# SoC_PS_504_DDR4.net
KiCad netlist of a schematic drawn in Altium Designer
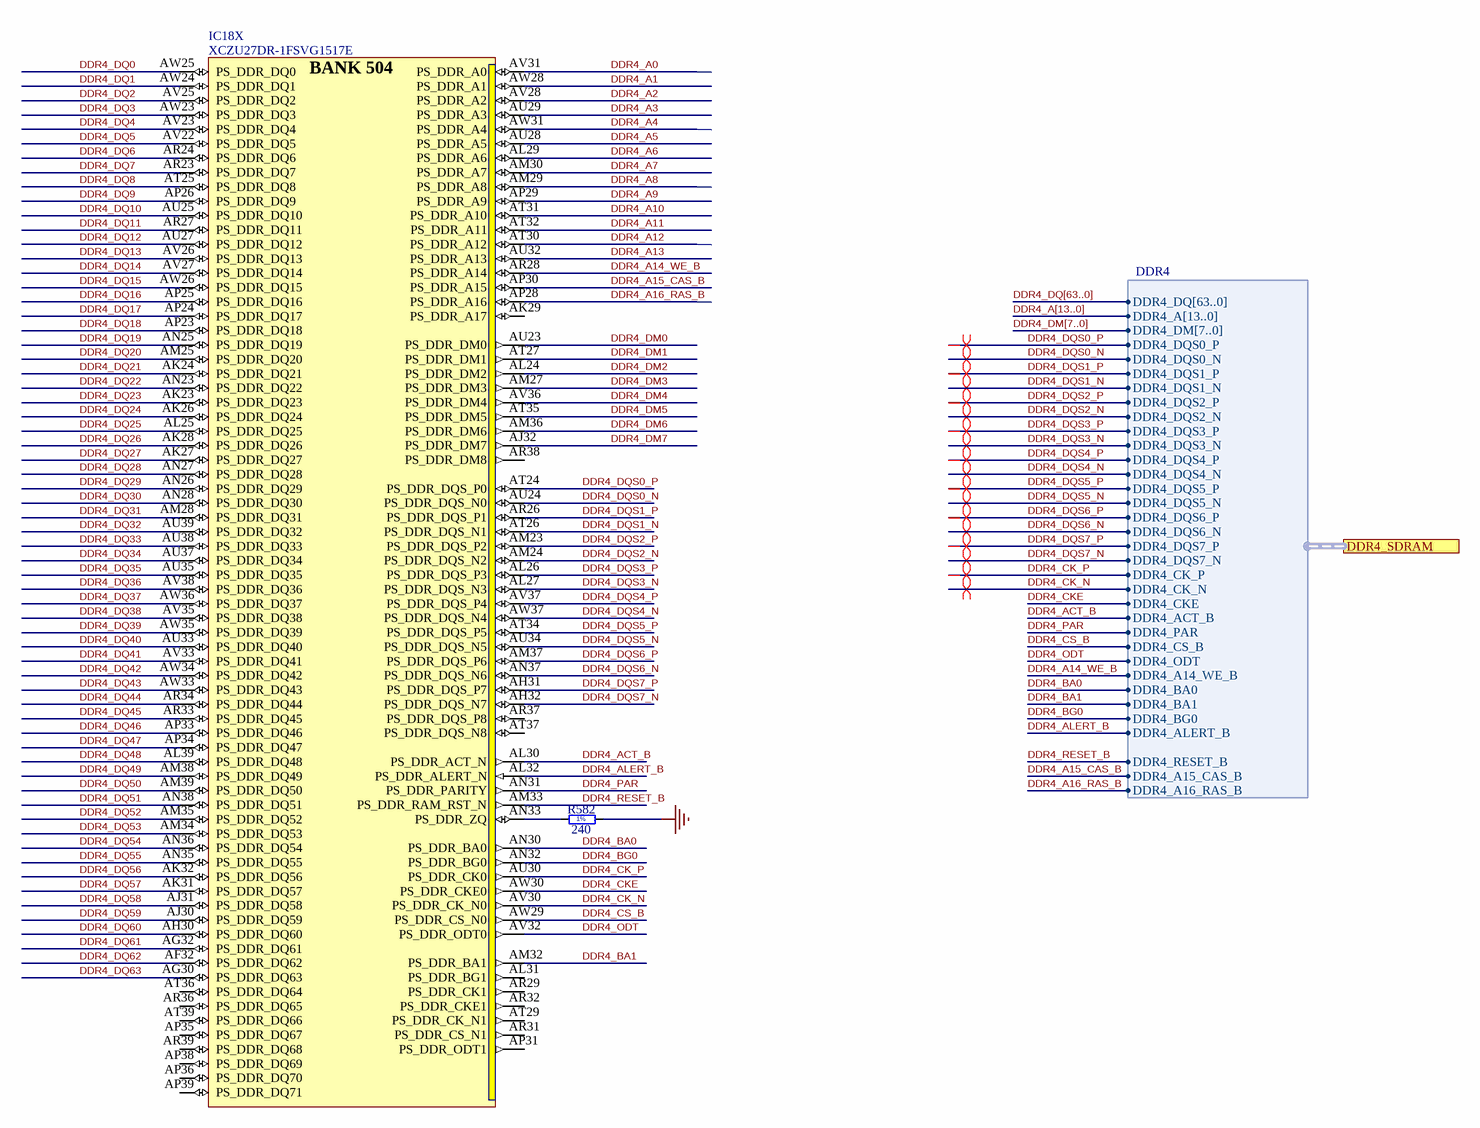
[diagram p0: SoC_PS_504_DDR4.SchDoc]

(export (version "E")
  (design (tool "Eeschema 10.0.6"))
  (components
    (comp (ref "IC18")
      (value "XCZU27DR-1FSVG1517E")
      (footprint "XILINX_FSVG1517 (XCZU27DR)")
      (fields (field (name "MANUFACTURER") "XILINX") (field (name "AUTHOR") "CERN DEM MR"))
      (libsource (lib "ICs And Semiconductors") (part "XCZU27DR-1FSVG1517E"))
    )
    (comp (ref "R582")
      (value "240")
      (footprint "RESC1005X40N")
      (description "Resistor - 1%")
      (fields
        (field (name "MANUFACTURER PART NUMBER") "R0402_240R_1%_0.0625W_100PPM")
        (field (name "MANUFACTURER") "GENERIC")
        (field (name "AUTHOR") "CERN DEM JLC")
      )
      (libsource (lib "Resistors") (part "Resistor - 1%"))
    )
  )
  (nets
    (net (code "2") (name "/DDR4_A0") (class "Default")
      (node (ref "IC18") (pin "AV31") (pinfunction "PS_DDR_A0_AV31") (pintype "bidirectional"))
    )
    (net (code "3") (name "/DDR4_A1") (class "Default")
      (node (ref "IC18") (pin "AW28") (pinfunction "PS_DDR_A1_AW28") (pintype "bidirectional"))
    )
    (net (code "4") (name "/DDR4_A2") (class "Default")
      (node (ref "IC18") (pin "AV28") (pinfunction "PS_DDR_A2_AV28") (pintype "bidirectional"))
    )
    (net (code "5") (name "/DDR4_A3") (class "Default")
      (node (ref "IC18") (pin "AU29") (pinfunction "PS_DDR_A3_AU29") (pintype "bidirectional"))
    )
    (net (code "6") (name "/DDR4_A4") (class "Default")
      (node (ref "IC18") (pin "AW31") (pinfunction "PS_DDR_A4_AW31") (pintype "bidirectional"))
    )
    (net (code "7") (name "/DDR4_A5") (class "Default")
      (node (ref "IC18") (pin "AU28") (pinfunction "PS_DDR_A5_AU28") (pintype "bidirectional"))
    )
    (net (code "8") (name "/DDR4_A6") (class "Default")
      (node (ref "IC18") (pin "AL29") (pinfunction "PS_DDR_A6_AL29") (pintype "bidirectional"))
    )
    (net (code "9") (name "/DDR4_A7") (class "Default")
      (node (ref "IC18") (pin "AM30") (pinfunction "PS_DDR_A7_AM30") (pintype "bidirectional"))
    )
    (net (code "10") (name "/DDR4_A8") (class "Default")
      (node (ref "IC18") (pin "AM29") (pinfunction "PS_DDR_A8_AM29") (pintype "bidirectional"))
    )
    (net (code "11") (name "/DDR4_A9") (class "Default")
      (node (ref "IC18") (pin "AP29") (pinfunction "PS_DDR_A9_AP29") (pintype "bidirectional"))
    )
    (net (code "12") (name "/DDR4_A10") (class "Default")
      (node (ref "IC18") (pin "AT31") (pinfunction "PS_DDR_A10_AT31") (pintype "bidirectional"))
    )
    (net (code "13") (name "/DDR4_A11") (class "Default")
      (node (ref "IC18") (pin "AT32") (pinfunction "PS_DDR_A11_AT32") (pintype "bidirectional"))
    )
    (net (code "14") (name "/DDR4_A12") (class "Default")
      (node (ref "IC18") (pin "AT30") (pinfunction "PS_DDR_A12_AT30") (pintype "bidirectional"))
    )
    (net (code "15") (name "/DDR4_A13") (class "Default")
      (node (ref "IC18") (pin "AU32") (pinfunction "PS_DDR_A13_AU32") (pintype "bidirectional"))
    )
    (net (code "16") (name "/DDR4_A14_WE_B") (class "Default")
      (node (ref "IC18") (pin "AR28") (pinfunction "PS_DDR_A14_AR28") (pintype "bidirectional"))
    )
    (net (code "17") (name "/DDR4_A15_CAS_B") (class "Default")
      (node (ref "IC18") (pin "AP30") (pinfunction "PS_DDR_A15_AP30") (pintype "bidirectional"))
    )
    (net (code "18") (name "/DDR4_A16_RAS_B") (class "Default")
      (node (ref "IC18") (pin "AP28") (pinfunction "PS_DDR_A16_AP28") (pintype "bidirectional"))
    )
    (net (code "19") (name "/DDR4_ACT_B") (class "Default")
      (node (ref "IC18") (pin "AL30") (pinfunction "PS_DDR_ACT_N_AL30") (pintype "output"))
    )
    (net (code "20") (name "/DDR4_ALERT_B") (class "Default")
      (node (ref "IC18") (pin "AL32") (pinfunction "PS_DDR_ALERT_N_AL32") (pintype "input"))
    )
    (net (code "22") (name "/DDR4_BA0") (class "Default")
      (node (ref "IC18") (pin "AN30") (pinfunction "PS_DDR_BA0_AN30") (pintype "output"))
    )
    (net (code "23") (name "/DDR4_BA1") (class "Default")
      (node (ref "IC18") (pin "AM32") (pinfunction "PS_DDR_BA1_AM32") (pintype "output"))
    )
    (net (code "24") (name "/DDR4_BG0") (class "Default")
      (node (ref "IC18") (pin "AN32") (pinfunction "PS_DDR_BG0_AN32") (pintype "output"))
    )
    (net (code "25") (name "/DDR4_CKE") (class "Default")
      (node (ref "IC18") (pin "AW30") (pinfunction "PS_DDR_CKE0_AW30") (pintype "output"))
    )
    (net (code "26") (name "/DDR4_CK_N") (class "Default")
      (node (ref "IC18") (pin "AV30") (pinfunction "PS_DDR_CK_N0_AV30") (pintype "output"))
    )
    (net (code "27") (name "/DDR4_CK_P") (class "Default")
      (node (ref "IC18") (pin "AU30") (pinfunction "PS_DDR_CK0_AU30") (pintype "output"))
    )
    (net (code "28") (name "/DDR4_CS_B") (class "Default")
      (node (ref "IC18") (pin "AW29") (pinfunction "PS_DDR_CS_N0_AW29") (pintype "output"))
    )
    (net (code "29") (name "/DDR4_DM0") (class "Default")
      (node (ref "IC18") (pin "AU23") (pinfunction "PS_DDR_DM0_AU23") (pintype "output"))
    )
    (net (code "30") (name "/DDR4_DM1") (class "Default")
      (node (ref "IC18") (pin "AT27") (pinfunction "PS_DDR_DM1_AT27") (pintype "output"))
    )
    (net (code "31") (name "/DDR4_DM2") (class "Default")
      (node (ref "IC18") (pin "AL24") (pinfunction "PS_DDR_DM2_AL24") (pintype "output"))
    )
    (net (code "32") (name "/DDR4_DM3") (class "Default")
      (node (ref "IC18") (pin "AM27") (pinfunction "PS_DDR_DM3_AM27") (pintype "output"))
    )
    (net (code "33") (name "/DDR4_DM4") (class "Default")
      (node (ref "IC18") (pin "AV36") (pinfunction "PS_DDR_DM4_AV36") (pintype "output"))
    )
    (net (code "34") (name "/DDR4_DM5") (class "Default")
      (node (ref "IC18") (pin "AT35") (pinfunction "PS_DDR_DM5_AT35") (pintype "output"))
    )
    (net (code "35") (name "/DDR4_DM6") (class "Default")
      (node (ref "IC18") (pin "AM36") (pinfunction "PS_DDR_DM6_AM36") (pintype "output"))
    )
    (net (code "36") (name "/DDR4_DM7") (class "Default")
      (node (ref "IC18") (pin "AJ32") (pinfunction "PS_DDR_DM7_AJ32") (pintype "output"))
    )
    (net (code "38") (name "/DDR4_DQ0") (class "Default")
      (node (ref "IC18") (pin "AW25") (pinfunction "PS_DDR_DQ0_AW25") (pintype "bidirectional"))
    )
    (net (code "39") (name "/DDR4_DQ1") (class "Default")
      (node (ref "IC18") (pin "AW24") (pinfunction "PS_DDR_DQ1_AW24") (pintype "bidirectional"))
    )
    (net (code "40") (name "/DDR4_DQ2") (class "Default")
      (node (ref "IC18") (pin "AV25") (pinfunction "PS_DDR_DQ2_AV25") (pintype "bidirectional"))
    )
    (net (code "41") (name "/DDR4_DQ3") (class "Default")
      (node (ref "IC18") (pin "AW23") (pinfunction "PS_DDR_DQ3_AW23") (pintype "bidirectional"))
    )
    (net (code "42") (name "/DDR4_DQ4") (class "Default")
      (node (ref "IC18") (pin "AV23") (pinfunction "PS_DDR_DQ4_AV23") (pintype "bidirectional"))
    )
    (net (code "43") (name "/DDR4_DQ5") (class "Default")
      (node (ref "IC18") (pin "AV22") (pinfunction "PS_DDR_DQ5_AV22") (pintype "bidirectional"))
    )
    (net (code "44") (name "/DDR4_DQ6") (class "Default")
      (node (ref "IC18") (pin "AR24") (pinfunction "PS_DDR_DQ6_AR24") (pintype "bidirectional"))
    )
    (net (code "45") (name "/DDR4_DQ7") (class "Default")
      (node (ref "IC18") (pin "AR23") (pinfunction "PS_DDR_DQ7_AR23") (pintype "bidirectional"))
    )
    (net (code "46") (name "/DDR4_DQ8") (class "Default")
      (node (ref "IC18") (pin "AT25") (pinfunction "PS_DDR_DQ8_AT25") (pintype "bidirectional"))
    )
    (net (code "47") (name "/DDR4_DQ9") (class "Default")
      (node (ref "IC18") (pin "AP26") (pinfunction "PS_DDR_DQ9_AP26") (pintype "bidirectional"))
    )
    (net (code "48") (name "/DDR4_DQ10") (class "Default")
      (node (ref "IC18") (pin "AU25") (pinfunction "PS_DDR_DQ10_AU25") (pintype "bidirectional"))
    )
    (net (code "49") (name "/DDR4_DQ11") (class "Default")
      (node (ref "IC18") (pin "AR27") (pinfunction "PS_DDR_DQ11_AR27") (pintype "bidirectional"))
    )
    (net (code "50") (name "/DDR4_DQ12") (class "Default")
      (node (ref "IC18") (pin "AU27") (pinfunction "PS_DDR_DQ12_AU27") (pintype "bidirectional"))
    )
    (net (code "51") (name "/DDR4_DQ13") (class "Default")
      (node (ref "IC18") (pin "AV26") (pinfunction "PS_DDR_DQ13_AV26") (pintype "bidirectional"))
    )
    (net (code "52") (name "/DDR4_DQ14") (class "Default")
      (node (ref "IC18") (pin "AV27") (pinfunction "PS_DDR_DQ14_AV27") (pintype "bidirectional"))
    )
    (net (code "53") (name "/DDR4_DQ15") (class "Default")
      (node (ref "IC18") (pin "AW26") (pinfunction "PS_DDR_DQ15_AW26") (pintype "bidirectional"))
    )
    (net (code "54") (name "/DDR4_DQ16") (class "Default")
      (node (ref "IC18") (pin "AP25") (pinfunction "PS_DDR_DQ16_AP25") (pintype "bidirectional"))
    )
    (net (code "55") (name "/DDR4_DQ17") (class "Default")
      (node (ref "IC18") (pin "AP24") (pinfunction "PS_DDR_DQ17_AP24") (pintype "bidirectional"))
    )
    (net (code "56") (name "/DDR4_DQ18") (class "Default")
      (node (ref "IC18") (pin "AP23") (pinfunction "PS_DDR_DQ18_AP23") (pintype "bidirectional"))
    )
    (net (code "57") (name "/DDR4_DQ19") (class "Default")
      (node (ref "IC18") (pin "AN25") (pinfunction "PS_DDR_DQ19_AN25") (pintype "bidirectional"))
    )
    (net (code "58") (name "/DDR4_DQ20") (class "Default")
      (node (ref "IC18") (pin "AM25") (pinfunction "PS_DDR_DQ20_AM25") (pintype "bidirectional"))
    )
    (net (code "59") (name "/DDR4_DQ21") (class "Default")
      (node (ref "IC18") (pin "AK24") (pinfunction "PS_DDR_DQ21_AK24") (pintype "bidirectional"))
    )
    (net (code "60") (name "/DDR4_DQ22") (class "Default")
      (node (ref "IC18") (pin "AN23") (pinfunction "PS_DDR_DQ22_AN23") (pintype "bidirectional"))
    )
    (net (code "61") (name "/DDR4_DQ23") (class "Default")
      (node (ref "IC18") (pin "AK23") (pinfunction "PS_DDR_DQ23_AK23") (pintype "bidirectional"))
    )
    (net (code "62") (name "/DDR4_DQ24") (class "Default")
      (node (ref "IC18") (pin "AK26") (pinfunction "PS_DDR_DQ24_AK26") (pintype "bidirectional"))
    )
    (net (code "63") (name "/DDR4_DQ25") (class "Default")
      (node (ref "IC18") (pin "AL25") (pinfunction "PS_DDR_DQ25_AL25") (pintype "bidirectional"))
    )
    (net (code "64") (name "/DDR4_DQ26") (class "Default")
      (node (ref "IC18") (pin "AK28") (pinfunction "PS_DDR_DQ26_AK28") (pintype "bidirectional"))
    )
    (net (code "65") (name "/DDR4_DQ27") (class "Default")
      (node (ref "IC18") (pin "AK27") (pinfunction "PS_DDR_DQ27_AK27") (pintype "bidirectional"))
    )
    (net (code "66") (name "/DDR4_DQ28") (class "Default")
      (node (ref "IC18") (pin "AN27") (pinfunction "PS_DDR_DQ28_AN27") (pintype "bidirectional"))
    )
    (net (code "67") (name "/DDR4_DQ29") (class "Default")
      (node (ref "IC18") (pin "AN26") (pinfunction "PS_DDR_DQ29_AN26") (pintype "bidirectional"))
    )
    (net (code "68") (name "/DDR4_DQ30") (class "Default")
      (node (ref "IC18") (pin "AN28") (pinfunction "PS_DDR_DQ30_AN28") (pintype "bidirectional"))
    )
    (net (code "69") (name "/DDR4_DQ31") (class "Default")
      (node (ref "IC18") (pin "AM28") (pinfunction "PS_DDR_DQ31_AM28") (pintype "bidirectional"))
    )
    (net (code "70") (name "/DDR4_DQ32") (class "Default")
      (node (ref "IC18") (pin "AU39") (pinfunction "PS_DDR_DQ32_AU39") (pintype "bidirectional"))
    )
    (net (code "71") (name "/DDR4_DQ33") (class "Default")
      (node (ref "IC18") (pin "AU38") (pinfunction "PS_DDR_DQ33_AU38") (pintype "bidirectional"))
    )
    (net (code "72") (name "/DDR4_DQ34") (class "Default")
      (node (ref "IC18") (pin "AU37") (pinfunction "PS_DDR_DQ34_AU37") (pintype "bidirectional"))
    )
    (net (code "73") (name "/DDR4_DQ35") (class "Default")
      (node (ref "IC18") (pin "AU35") (pinfunction "PS_DDR_DQ35_AU35") (pintype "bidirectional"))
    )
    (net (code "74") (name "/DDR4_DQ36") (class "Default")
      (node (ref "IC18") (pin "AV38") (pinfunction "PS_DDR_DQ36_AV38") (pintype "bidirectional"))
    )
    (net (code "75") (name "/DDR4_DQ37") (class "Default")
      (node (ref "IC18") (pin "AW36") (pinfunction "PS_DDR_DQ37_AW36") (pintype "bidirectional"))
    )
    (net (code "76") (name "/DDR4_DQ38") (class "Default")
      (node (ref "IC18") (pin "AV35") (pinfunction "PS_DDR_DQ38_AV35") (pintype "bidirectional"))
    )
    (net (code "77") (name "/DDR4_DQ39") (class "Default")
      (node (ref "IC18") (pin "AW35") (pinfunction "PS_DDR_DQ39_AW35") (pintype "bidirectional"))
    )
    (net (code "78") (name "/DDR4_DQ40") (class "Default")
      (node (ref "IC18") (pin "AU33") (pinfunction "PS_DDR_DQ40_AU33") (pintype "bidirectional"))
    )
    (net (code "79") (name "/DDR4_DQ41") (class "Default")
      (node (ref "IC18") (pin "AV33") (pinfunction "PS_DDR_DQ41_AV33") (pintype "bidirectional"))
    )
    (net (code "80") (name "/DDR4_DQ42") (class "Default")
      (node (ref "IC18") (pin "AW34") (pinfunction "PS_DDR_DQ42_AW34") (pintype "bidirectional"))
    )
    (net (code "81") (name "/DDR4_DQ43") (class "Default")
      (node (ref "IC18") (pin "AW33") (pinfunction "PS_DDR_DQ43_AW33") (pintype "bidirectional"))
    )
    (net (code "82") (name "/DDR4_DQ44") (class "Default")
      (node (ref "IC18") (pin "AR34") (pinfunction "PS_DDR_DQ44_AR34") (pintype "bidirectional"))
    )
    (net (code "83") (name "/DDR4_DQ45") (class "Default")
      (node (ref "IC18") (pin "AR33") (pinfunction "PS_DDR_DQ45_AR33") (pintype "bidirectional"))
    )
    (net (code "84") (name "/DDR4_DQ46") (class "Default")
      (node (ref "IC18") (pin "AP33") (pinfunction "PS_DDR_DQ46_AP33") (pintype "bidirectional"))
    )
    (net (code "85") (name "/DDR4_DQ47") (class "Default")
      (node (ref "IC18") (pin "AP34") (pinfunction "PS_DDR_DQ47_AP34") (pintype "bidirectional"))
    )
    (net (code "86") (name "/DDR4_DQ48") (class "Default")
      (node (ref "IC18") (pin "AL39") (pinfunction "PS_DDR_DQ48_AL39") (pintype "bidirectional"))
    )
    (net (code "87") (name "/DDR4_DQ49") (class "Default")
      (node (ref "IC18") (pin "AM38") (pinfunction "PS_DDR_DQ49_AM38") (pintype "bidirectional"))
    )
    (net (code "88") (name "/DDR4_DQ50") (class "Default")
      (node (ref "IC18") (pin "AM39") (pinfunction "PS_DDR_DQ50_AM39") (pintype "bidirectional"))
    )
    (net (code "89") (name "/DDR4_DQ51") (class "Default")
      (node (ref "IC18") (pin "AN38") (pinfunction "PS_DDR_DQ51_AN38") (pintype "bidirectional"))
    )
    (net (code "90") (name "/DDR4_DQ52") (class "Default")
      (node (ref "IC18") (pin "AM35") (pinfunction "PS_DDR_DQ52_AM35") (pintype "bidirectional"))
    )
    (net (code "91") (name "/DDR4_DQ53") (class "Default")
      (node (ref "IC18") (pin "AM34") (pinfunction "PS_DDR_DQ53_AM34") (pintype "bidirectional"))
    )
    (net (code "92") (name "/DDR4_DQ54") (class "Default")
      (node (ref "IC18") (pin "AN36") (pinfunction "PS_DDR_DQ54_AN36") (pintype "bidirectional"))
    )
    (net (code "93") (name "/DDR4_DQ55") (class "Default")
      (node (ref "IC18") (pin "AN35") (pinfunction "PS_DDR_DQ55_AN35") (pintype "bidirectional"))
    )
    (net (code "94") (name "/DDR4_DQ56") (class "Default")
      (node (ref "IC18") (pin "AK32") (pinfunction "PS_DDR_DQ56_AK32") (pintype "bidirectional"))
    )
    (net (code "95") (name "/DDR4_DQ57") (class "Default")
      (node (ref "IC18") (pin "AK31") (pinfunction "PS_DDR_DQ57_AK31") (pintype "bidirectional"))
    )
    (net (code "96") (name "/DDR4_DQ58") (class "Default")
      (node (ref "IC18") (pin "AJ31") (pinfunction "PS_DDR_DQ58_AJ31") (pintype "bidirectional"))
    )
    (net (code "97") (name "/DDR4_DQ59") (class "Default")
      (node (ref "IC18") (pin "AJ30") (pinfunction "PS_DDR_DQ59_AJ30") (pintype "bidirectional"))
    )
    (net (code "98") (name "/DDR4_DQ60") (class "Default")
      (node (ref "IC18") (pin "AH30") (pinfunction "PS_DDR_DQ60_AH30") (pintype "bidirectional"))
    )
    (net (code "99") (name "/DDR4_DQ61") (class "Default")
      (node (ref "IC18") (pin "AG32") (pinfunction "PS_DDR_DQ61_AG32") (pintype "bidirectional"))
    )
    (net (code "100") (name "/DDR4_DQ62") (class "Default")
      (node (ref "IC18") (pin "AF32") (pinfunction "PS_DDR_DQ62_AF32") (pintype "bidirectional"))
    )
    (net (code "101") (name "/DDR4_DQ63") (class "Default")
      (node (ref "IC18") (pin "AG30") (pinfunction "PS_DDR_DQ63_AG30") (pintype "bidirectional"))
    )
    (net (code "102") (name "/DDR4_DQS0_N") (class "Default")
      (node (ref "IC18") (pin "AU24") (pinfunction "PS_DDR_DQS_N0_AU24") (pintype "bidirectional"))
    )
    (net (code "103") (name "/DDR4_DQS0_P") (class "Default")
      (node (ref "IC18") (pin "AT24") (pinfunction "PS_DDR_DQS_P0_AT24") (pintype "bidirectional"))
    )
    (net (code "104") (name "/DDR4_DQS1_N") (class "Default")
      (node (ref "IC18") (pin "AT26") (pinfunction "PS_DDR_DQS_N1_AT26") (pintype "bidirectional"))
    )
    (net (code "105") (name "/DDR4_DQS1_P") (class "Default")
      (node (ref "IC18") (pin "AR26") (pinfunction "PS_DDR_DQS_P1_AR26") (pintype "bidirectional"))
    )
    (net (code "106") (name "/DDR4_DQS2_N") (class "Default")
      (node (ref "IC18") (pin "AM24") (pinfunction "PS_DDR_DQS_N2_AM24") (pintype "bidirectional"))
    )
    (net (code "107") (name "/DDR4_DQS2_P") (class "Default")
      (node (ref "IC18") (pin "AM23") (pinfunction "PS_DDR_DQS_P2_AM23") (pintype "bidirectional"))
    )
    (net (code "108") (name "/DDR4_DQS3_N") (class "Default")
      (node (ref "IC18") (pin "AL27") (pinfunction "PS_DDR_DQS_N3_AL27") (pintype "bidirectional"))
    )
    (net (code "109") (name "/DDR4_DQS3_P") (class "Default")
      (node (ref "IC18") (pin "AL26") (pinfunction "PS_DDR_DQS_P3_AL26") (pintype "bidirectional"))
    )
    (net (code "110") (name "/DDR4_DQS4_N") (class "Default")
      (node (ref "IC18") (pin "AW37") (pinfunction "PS_DDR_DQS_N4_AW37") (pintype "bidirectional"))
    )
    (net (code "111") (name "/DDR4_DQS4_P") (class "Default")
      (node (ref "IC18") (pin "AV37") (pinfunction "PS_DDR_DQS_P4_AV37") (pintype "bidirectional"))
    )
    (net (code "112") (name "/DDR4_DQS5_N") (class "Default")
      (node (ref "IC18") (pin "AU34") (pinfunction "PS_DDR_DQS_N5_AU34") (pintype "bidirectional"))
    )
    (net (code "113") (name "/DDR4_DQS5_P") (class "Default")
      (node (ref "IC18") (pin "AT34") (pinfunction "PS_DDR_DQS_P5_AT34") (pintype "bidirectional"))
    )
    (net (code "114") (name "/DDR4_DQS6_N") (class "Default")
      (node (ref "IC18") (pin "AN37") (pinfunction "PS_DDR_DQS_N6_AN37") (pintype "bidirectional"))
    )
    (net (code "115") (name "/DDR4_DQS6_P") (class "Default")
      (node (ref "IC18") (pin "AM37") (pinfunction "PS_DDR_DQS_P6_AM37") (pintype "bidirectional"))
    )
    (net (code "116") (name "/DDR4_DQS7_N") (class "Default")
      (node (ref "IC18") (pin "AH32") (pinfunction "PS_DDR_DQS_N7_AH32") (pintype "bidirectional"))
    )
    (net (code "117") (name "/DDR4_DQS7_P") (class "Default")
      (node (ref "IC18") (pin "AH31") (pinfunction "PS_DDR_DQS_P7_AH31") (pintype "bidirectional"))
    )
    (net (code "119") (name "/DDR4_ODT") (class "Default")
      (node (ref "IC18") (pin "AV32") (pinfunction "PS_DDR_ODT0_AV32") (pintype "output"))
    )
    (net (code "120") (name "/DDR4_PAR") (class "Default")
      (node (ref "IC18") (pin "AN31") (pinfunction "PS_DDR_PARITY_AN31") (pintype "output"))
    )
    (net (code "121") (name "/DDR4_RESET_B") (class "Default")
      (node (ref "IC18") (pin "AM33") (pinfunction "PS_DDR_RAM_RST_N_AM33") (pintype "output"))
    )
    (net (code "123") (name "GND") (class "Default")
      (node (ref "R582") (pin "2") (pinfunction "2_2") (pintype "passive"))
    )
    (net (code "124") (name "Net-(IC18X-PS_DDR_ZQ)") (class "Default")
      (node (ref "IC18") (pin "AN33") (pinfunction "PS_DDR_ZQ_AN33") (pintype "bidirectional"))
      (node (ref "R582") (pin "1") (pinfunction "1_1") (pintype "passive"))
    )
    (net (code "125") (name "unconnected-(IC18X-PS_DDR_A17-PadAK29)") (class "Default")
      (node (ref "IC18") (pin "AK29") (pinfunction "PS_DDR_A17_AK29") (pintype "bidirectional"))
    )
    (net (code "126") (name "unconnected-(IC18X-PS_DDR_BG1-PadAL31)") (class "Default")
      (node (ref "IC18") (pin "AL31") (pinfunction "PS_DDR_BG1_AL31") (pintype "output"))
    )
    (net (code "127") (name "unconnected-(IC18X-PS_DDR_CK1-PadAR29)") (class "Default")
      (node (ref "IC18") (pin "AR29") (pinfunction "PS_DDR_CK1_AR29") (pintype "output"))
    )
    (net (code "128") (name "unconnected-(IC18X-PS_DDR_CKE1-PadAR32)") (class "Default")
      (node (ref "IC18") (pin "AR32") (pinfunction "PS_DDR_CKE1_AR32") (pintype "output"))
    )
    (net (code "129") (name "unconnected-(IC18X-PS_DDR_CK_N1-PadAT29)") (class "Default")
      (node (ref "IC18") (pin "AT29") (pinfunction "PS_DDR_CK_N1_AT29") (pintype "output"))
    )
    (net (code "130") (name "unconnected-(IC18X-PS_DDR_CS_N1-PadAR31)") (class "Default")
      (node (ref "IC18") (pin "AR31") (pinfunction "PS_DDR_CS_N1_AR31") (pintype "output"))
    )
    (net (code "131") (name "unconnected-(IC18X-PS_DDR_DM8-PadAR38)") (class "Default")
      (node (ref "IC18") (pin "AR38") (pinfunction "PS_DDR_DM8_AR38") (pintype "output"))
    )
    (net (code "132") (name "unconnected-(IC18X-PS_DDR_DQ64-PadAT36)") (class "Default")
      (node (ref "IC18") (pin "AT36") (pinfunction "PS_DDR_DQ64_AT36") (pintype "bidirectional"))
    )
    (net (code "133") (name "unconnected-(IC18X-PS_DDR_DQ65-PadAR36)") (class "Default")
      (node (ref "IC18") (pin "AR36") (pinfunction "PS_DDR_DQ65_AR36") (pintype "bidirectional"))
    )
    (net (code "134") (name "unconnected-(IC18X-PS_DDR_DQ66-PadAT39)") (class "Default")
      (node (ref "IC18") (pin "AT39") (pinfunction "PS_DDR_DQ66_AT39") (pintype "bidirectional"))
    )
    (net (code "135") (name "unconnected-(IC18X-PS_DDR_DQ67-PadAP35)") (class "Default")
      (node (ref "IC18") (pin "AP35") (pinfunction "PS_DDR_DQ67_AP35") (pintype "bidirectional"))
    )
    (net (code "136") (name "unconnected-(IC18X-PS_DDR_DQ68-PadAR39)") (class "Default")
      (node (ref "IC18") (pin "AR39") (pinfunction "PS_DDR_DQ68_AR39") (pintype "bidirectional"))
    )
    (net (code "137") (name "unconnected-(IC18X-PS_DDR_DQ69-PadAP38)") (class "Default")
      (node (ref "IC18") (pin "AP38") (pinfunction "PS_DDR_DQ69_AP38") (pintype "bidirectional"))
    )
    (net (code "138") (name "unconnected-(IC18X-PS_DDR_DQ70-PadAP36)") (class "Default")
      (node (ref "IC18") (pin "AP36") (pinfunction "PS_DDR_DQ70_AP36") (pintype "bidirectional"))
    )
    (net (code "139") (name "unconnected-(IC18X-PS_DDR_DQ71-PadAP39)") (class "Default")
      (node (ref "IC18") (pin "AP39") (pinfunction "PS_DDR_DQ71_AP39") (pintype "bidirectional"))
    )
    (net (code "140") (name "unconnected-(IC18X-PS_DDR_DQS_N8-PadAT37)") (class "Default")
      (node (ref "IC18") (pin "AT37") (pinfunction "PS_DDR_DQS_N8_AT37") (pintype "bidirectional"))
    )
    (net (code "141") (name "unconnected-(IC18X-PS_DDR_DQS_P8-PadAR37)") (class "Default")
      (node (ref "IC18") (pin "AR37") (pinfunction "PS_DDR_DQS_P8_AR37") (pintype "bidirectional"))
    )
    (net (code "142") (name "unconnected-(IC18X-PS_DDR_ODT1-PadAP31)") (class "Default")
      (node (ref "IC18") (pin "AP31") (pinfunction "PS_DDR_ODT1_AP31") (pintype "output"))
    )
  )
)
